# charger_1_2.net
KiCad netlist of a schematic drawn in EAGLE
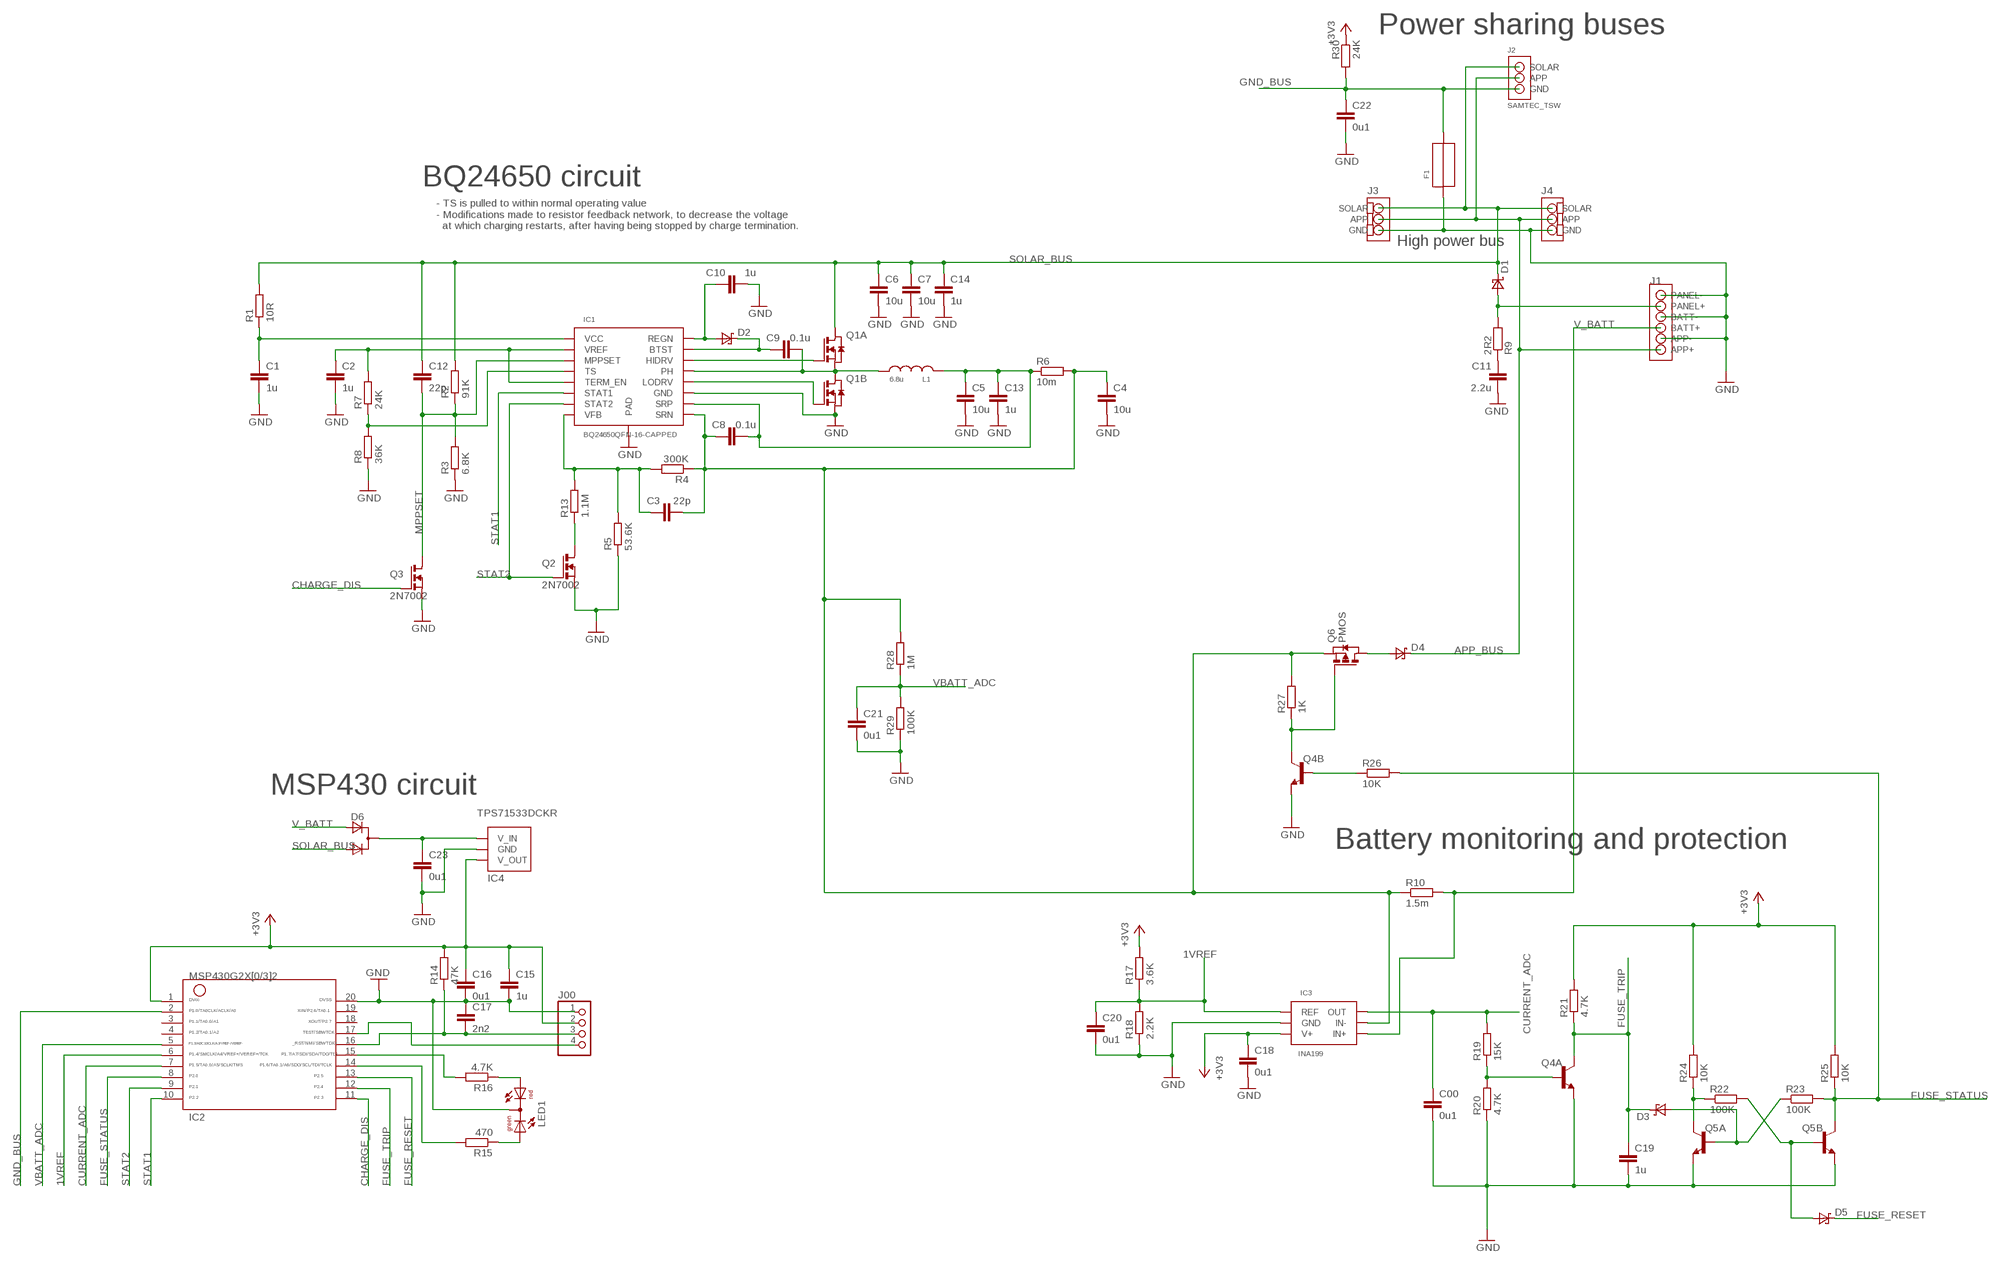
[diagram p0: schematic, sheet 1]

(export (version "E")
  (design (tool "Eeschema 10.0.6"))
  (components
    (comp (ref "C00")
      (value "0u1")
      (footprint "eagle-import:C0603K")
      (libsource (lib "eagle-import") (part "C-EUC0603K"))
    )
    (comp (ref "C1")
      (value "1u")
      (footprint "eagle-import:C0603")
      (libsource (lib "eagle-import") (part "C-EUC0603"))
    )
    (comp (ref "C2")
      (value "1u")
      (footprint "eagle-import:C0603")
      (libsource (lib "eagle-import") (part "C-EUC0603"))
    )
    (comp (ref "C3")
      (value "22p")
      (footprint "eagle-import:C0603")
      (libsource (lib "eagle-import") (part "C-EUC0603"))
    )
    (comp (ref "C4")
      (value "10u")
      (footprint "eagle-import:C1206")
      (libsource (lib "eagle-import") (part "C-EUC1206"))
    )
    (comp (ref "C5")
      (value "10u")
      (footprint "eagle-import:C1206")
      (libsource (lib "eagle-import") (part "C-EUC1206"))
    )
    (comp (ref "C6")
      (value "10u")
      (footprint "eagle-import:C1206")
      (libsource (lib "eagle-import") (part "C-EUC1206"))
    )
    (comp (ref "C7")
      (value "10u")
      (footprint "eagle-import:C1206")
      (libsource (lib "eagle-import") (part "C-EUC1206"))
    )
    (comp (ref "C8")
      (value "0.1u")
      (footprint "eagle-import:C0603")
      (libsource (lib "eagle-import") (part "C-EUC0603"))
    )
    (comp (ref "C9")
      (value "0.1u")
      (footprint "eagle-import:C0603")
      (libsource (lib "eagle-import") (part "C-EUC0603"))
    )
    (comp (ref "C10")
      (value "1u")
      (footprint "eagle-import:C0603")
      (libsource (lib "eagle-import") (part "C-EUC0603"))
    )
    (comp (ref "C11")
      (value "2.2u")
      (footprint "eagle-import:C0603")
      (libsource (lib "eagle-import") (part "C-EUC0603"))
    )
    (comp (ref "C12")
      (value "22p")
      (footprint "eagle-import:C0603")
      (libsource (lib "eagle-import") (part "C-EUC0603"))
    )
    (comp (ref "C13")
      (value "1u")
      (footprint "eagle-import:C0603")
      (libsource (lib "eagle-import") (part "C-EUC0603"))
    )
    (comp (ref "C14")
      (value "1u")
      (footprint "eagle-import:C0603")
      (libsource (lib "eagle-import") (part "C-EUC0603"))
    )
    (comp (ref "C15")
      (value "1u")
      (footprint "eagle-import:C0603K")
      (libsource (lib "eagle-import") (part "C-EUC0603K"))
    )
    (comp (ref "C16")
      (value "0u1")
      (footprint "eagle-import:C0603K")
      (libsource (lib "eagle-import") (part "C-EUC0603K"))
    )
    (comp (ref "C17")
      (value "2n2")
      (footprint "eagle-import:C0603K")
      (libsource (lib "eagle-import") (part "C-EUC0603K"))
    )
    (comp (ref "C18")
      (value "0u1")
      (footprint "eagle-import:C0603K")
      (libsource (lib "eagle-import") (part "C-EUC0603K"))
    )
    (comp (ref "C19")
      (value "1u")
      (footprint "eagle-import:C0603")
      (libsource (lib "eagle-import") (part "C-EUC0603"))
    )
    (comp (ref "C20")
      (value "0u1")
      (footprint "eagle-import:C0603K")
      (libsource (lib "eagle-import") (part "C-EUC0603K"))
    )
    (comp (ref "C21")
      (value "0u1")
      (footprint "eagle-import:C0603K")
      (libsource (lib "eagle-import") (part "C-EUC0603K"))
    )
    (comp (ref "C22")
      (value "0u1")
      (footprint "eagle-import:C0603K")
      (libsource (lib "eagle-import") (part "C-EUC0603K"))
    )
    (comp (ref "C23")
      (value "0u1")
      (footprint "eagle-import:C0603K")
      (libsource (lib "eagle-import") (part "C-EUC0603K"))
    )
    (comp (ref "D1")
      (value "SCHOTTKYDPAK")
      (footprint "eagle-import:DPAK")
      (libsource (lib "eagle-import") (part "SCHOTTKYDPAK"))
    )
    (comp (ref "D2")
      (value "SCHOTTKYSOT23")
      (footprint "eagle-import:SOT23")
      (libsource (lib "eagle-import") (part "SCHOTTKYSOT23"))
    )
    (comp (ref "D3")
      (value "SCHOTTKYSOD-523F")
      (footprint "eagle-import:SOD-523F")
      (libsource (lib "eagle-import") (part "SCHOTTKYSOD-523F"))
    )
    (comp (ref "D4")
      (value "SCHOTTKYSO8-FLAT")
      (footprint "eagle-import:SO8-FLAT")
      (libsource (lib "eagle-import") (part "SCHOTTKYSO8-FLAT"))
    )
    (comp (ref "D5")
      (value "SCHOTTKYSOD-523F")
      (footprint "eagle-import:SOD-523F")
      (libsource (lib "eagle-import") (part "SCHOTTKYSOD-523F"))
    )
    (comp (ref "D6")
      (value "D_2ASOT23")
      (footprint "eagle-import:SOT-23")
      (libsource (lib "eagle-import") (part "D_2ASOT23"))
    )
    (comp (ref "F1")
      (value "FUSE2920")
      (footprint "eagle-import:2920")
      (libsource (lib "eagle-import") (part "FUSE2920"))
    )
    (comp (ref "IC1")
      (value "BQ24650QFN-16-CAPPED")
      (footprint "eagle-import:QFN-16-CAPPED")
      (libsource (lib "eagle-import") (part "BQ24650QFN-16-CAPPED"))
    )
    (comp (ref "IC2")
      (value "G2X[0/3]2---PW20")
      (footprint "eagle-import:PW20")
      (libsource (lib "eagle-import") (part "G2X[0/3]2---PW20"))
    )
    (comp (ref "IC3")
      (value "INA199")
      (footprint "eagle-import:SC70-6")
      (libsource (lib "eagle-import") (part "INA199"))
    )
    (comp (ref "IC4")
      (value "TPS71533DCKR")
      (footprint "eagle-import:SC70-5")
      (libsource (lib "eagle-import") (part "TPS71533DCKR"))
    )
    (comp (ref "J00")
      (value "PINHD-1X4")
      (footprint "eagle-import:1X04")
      (libsource (lib "eagle-import") (part "PINHD-1X4"))
    )
    (comp (ref "J1")
      (value "TERMINALBLOCK")
      (footprint "eagle-import:TERMINALBLOCK")
      (libsource (lib "eagle-import") (part "TERMINALBLOCK"))
    )
    (comp (ref "J2")
      (value "SAMTEC_TSW")
      (footprint "eagle-import:SAMTEC_TSW")
      (libsource (lib "eagle-import") (part "SAMTEC_TSW"))
    )
    (comp (ref "J3")
      (value "TERMINALBLOCK_3_REV")
      (footprint "eagle-import:TERMINALBLOCK_3_REV")
      (libsource (lib "eagle-import") (part "TERMINALBLOCK_3_REV"))
    )
    (comp (ref "J4")
      (value "TERMINALBLOCK_3")
      (footprint "eagle-import:TERMINALBLOCK_3")
      (libsource (lib "eagle-import") (part "TERMINALBLOCK_3"))
    )
    (comp (ref "L1")
      (value "6.8u")
      (footprint "eagle-import:INDUCTOR")
      (libsource (lib "eagle-import") (part "MULTICOMPINDUCTOR"))
    )
    (comp (ref "LED1")
      (value "DUOLED5MM")
      (footprint "eagle-import:DUOLED5MM")
      (libsource (lib "eagle-import") (part "DUOLED5MM"))
    )
    (comp (ref "Q1")
      (value "SI7288DP")
      (footprint "eagle-import:POWERPAK-SO8-DUAL")
      (libsource (lib "eagle-import") (part "SI7288DP"))
    )
    (comp (ref "Q2")
      (value "2N7002")
      (footprint "eagle-import:SOT23")
      (libsource (lib "eagle-import") (part "2N7002"))
    )
    (comp (ref "Q3")
      (value "2N7002")
      (footprint "eagle-import:SOT23")
      (libsource (lib "eagle-import") (part "2N7002"))
    )
    (comp (ref "Q4")
      (value "DUALNPN")
      (footprint "eagle-import:SC70-6")
      (libsource (lib "eagle-import") (part "DUALNPN"))
    )
    (comp (ref "Q5")
      (value "DUALNPN")
      (footprint "eagle-import:SC70-6")
      (libsource (lib "eagle-import") (part "DUALNPN"))
    )
    (comp (ref "Q6")
      (value "PMOS")
      (footprint "eagle-import:POWERPAK-SO8")
      (libsource (lib "eagle-import") (part "PMOS"))
    )
    (comp (ref "R1")
      (value "10R")
      (footprint "eagle-import:R0603")
      (libsource (lib "eagle-import") (part "R-EU_R0603"))
    )
    (comp (ref "R2")
      (value "91K")
      (footprint "eagle-import:R0603")
      (libsource (lib "eagle-import") (part "R-EU_R0603"))
    )
    (comp (ref "R3")
      (value "6.8K")
      (footprint "eagle-import:R0603")
      (libsource (lib "eagle-import") (part "R-EU_R0603"))
    )
    (comp (ref "R4")
      (value "300K")
      (footprint "eagle-import:R0603")
      (libsource (lib "eagle-import") (part "R-EU_R0603"))
    )
    (comp (ref "R5")
      (value "53.6K")
      (footprint "eagle-import:R0805")
      (libsource (lib "eagle-import") (part "R-EU_R0805"))
    )
    (comp (ref "R6")
      (value "10m")
      (footprint "eagle-import:R1206")
      (libsource (lib "eagle-import") (part "R-EU_R1206"))
    )
    (comp (ref "R7")
      (value "24K")
      (footprint "eagle-import:R0603")
      (libsource (lib "eagle-import") (part "R-EU_R0603"))
    )
    (comp (ref "R8")
      (value "36K")
      (footprint "eagle-import:R0603")
      (libsource (lib "eagle-import") (part "R-EU_R0603"))
    )
    (comp (ref "R9")
      (value "2R2")
      (footprint "eagle-import:R0603")
      (libsource (lib "eagle-import") (part "R-EU_R0603"))
    )
    (comp (ref "R10")
      (value "1.5m")
      (footprint "eagle-import:R2010")
      (libsource (lib "eagle-import") (part "R-EU_R2010"))
    )
    (comp (ref "R13")
      (value "1.1M")
      (footprint "eagle-import:R0603")
      (libsource (lib "eagle-import") (part "R-EU_R0603"))
    )
    (comp (ref "R14")
      (value "47K")
      (footprint "eagle-import:R0603")
      (libsource (lib "eagle-import") (part "R-EU_R0603"))
    )
    (comp (ref "R15")
      (value "470")
      (footprint "eagle-import:R0603")
      (libsource (lib "eagle-import") (part "resistor_R-EU_R0603"))
    )
    (comp (ref "R16")
      (value "4.7K")
      (footprint "eagle-import:R0603")
      (libsource (lib "eagle-import") (part "resistor_R-EU_R0603"))
    )
    (comp (ref "R17")
      (value "3.6K")
      (footprint "eagle-import:R0603")
      (libsource (lib "eagle-import") (part "R-EU_R0603"))
    )
    (comp (ref "R18")
      (value "2.2K")
      (footprint "eagle-import:R0603")
      (libsource (lib "eagle-import") (part "R-EU_R0603"))
    )
    (comp (ref "R19")
      (value "15K")
      (footprint "eagle-import:R0603")
      (libsource (lib "eagle-import") (part "R-EU_R0603"))
    )
    (comp (ref "R20")
      (value "4.7K")
      (footprint "eagle-import:R0603")
      (libsource (lib "eagle-import") (part "R-EU_R0603"))
    )
    (comp (ref "R21")
      (value "4.7K")
      (footprint "eagle-import:R0603")
      (libsource (lib "eagle-import") (part "R-EU_R0603"))
    )
    (comp (ref "R22")
      (value "100K")
      (footprint "eagle-import:R0603")
      (libsource (lib "eagle-import") (part "R-EU_R0603"))
    )
    (comp (ref "R23")
      (value "100K")
      (footprint "eagle-import:R0603")
      (libsource (lib "eagle-import") (part "R-EU_R0603"))
    )
    (comp (ref "R24")
      (value "10K")
      (footprint "eagle-import:R0603")
      (libsource (lib "eagle-import") (part "R-EU_R0603"))
    )
    (comp (ref "R25")
      (value "10K")
      (footprint "eagle-import:R0603")
      (libsource (lib "eagle-import") (part "R-EU_R0603"))
    )
    (comp (ref "R26")
      (value "10K")
      (footprint "eagle-import:R0603")
      (libsource (lib "eagle-import") (part "R-EU_R0603"))
    )
    (comp (ref "R27")
      (value "1K")
      (footprint "eagle-import:R0603")
      (libsource (lib "eagle-import") (part "R-EU_R0603"))
    )
    (comp (ref "R28")
      (value "1M")
      (footprint "eagle-import:R0805")
      (libsource (lib "eagle-import") (part "R-EU_R0805"))
    )
    (comp (ref "R29")
      (value "100K")
      (footprint "eagle-import:R0603")
      (libsource (lib "eagle-import") (part "R-EU_R0603"))
    )
    (comp (ref "R30")
      (value "24K")
      (footprint "eagle-import:R0603")
      (libsource (lib "eagle-import") (part "R-EU_R0603"))
    )
  )
  (nets
    (net (code "1") (name "+3V3") (class "Default")
      (node (ref "C15") (pin "1") (pinfunction "1_1") (pintype "passive"))
      (node (ref "C16") (pin "1") (pinfunction "1_1") (pintype "passive"))
      (node (ref "C18") (pin "1") (pinfunction "1_1") (pintype "passive"))
      (node (ref "IC2") (pin "1") (pinfunction "1_1") (pintype "bidirectional"))
      (node (ref "IC3") (pin "COLLECTOR-A-3") (pinfunction "V+_COLLECTOR-A-3") (pintype "bidirectional"))
      (node (ref "IC4") (pin "OUT") (pinfunction "V_OUT_OUT") (pintype "bidirectional"))
      (node (ref "J00") (pin "2") (pinfunction "2_2") (pintype "passive"))
      (node (ref "R14") (pin "2") (pinfunction "2_2") (pintype "passive"))
      (node (ref "R17") (pin "2") (pinfunction "2_2") (pintype "passive"))
      (node (ref "R21") (pin "2") (pinfunction "2_2") (pintype "passive"))
      (node (ref "R24") (pin "2") (pinfunction "2_2") (pintype "passive"))
      (node (ref "R25") (pin "2") (pinfunction "2_2") (pintype "passive"))
      (node (ref "R30") (pin "1") (pinfunction "1_1") (pintype "passive"))
    )
    (net (code "2") (name "/1VREF") (class "Default")
      (node (ref "C20") (pin "1") (pinfunction "1_1") (pintype "passive"))
      (node (ref "IC2") (pin "6") (pinfunction "6_6") (pintype "bidirectional"))
      (node (ref "IC3") (pin "EMITTER-B-1") (pinfunction "REF_EMITTER-B-1") (pintype "bidirectional"))
      (node (ref "R17") (pin "1") (pinfunction "1_1") (pintype "passive"))
      (node (ref "R18") (pin "2") (pinfunction "2_2") (pintype "passive"))
    )
    (net (code "3") (name "/APP_BUS") (class "Default")
      (node (ref "D4") (pin "CATHODE") (pinfunction "CATHODE_CATHODE") (pintype "passive"))
      (node (ref "J1") (pin "APP+") (pinfunction "APP+_APP+") (pintype "bidirectional"))
      (node (ref "J2") (pin "APP") (pinfunction "APP_APP") (pintype "bidirectional"))
      (node (ref "J3") (pin "APP") (pinfunction "APP_APP") (pintype "bidirectional"))
      (node (ref "J4") (pin "APP") (pinfunction "APP_APP") (pintype "bidirectional"))
    )
    (net (code "4") (name "/CHARGE_DIS") (class "Default")
      (node (ref "IC2") (pin "11") (pinfunction "11_11") (pintype "bidirectional"))
      (node (ref "Q3") (pin "ANODE") (pinfunction "G_ANODE") (pintype "passive"))
    )
    (net (code "5") (name "/CURRENT_ADC") (class "Default")
      (node (ref "C00") (pin "1") (pinfunction "1_1") (pintype "passive"))
      (node (ref "IC2") (pin "7") (pinfunction "7_7") (pintype "bidirectional"))
      (node (ref "IC3") (pin "COLLECTOR-B-6") (pinfunction "OUT_COLLECTOR-B-6") (pintype "bidirectional"))
      (node (ref "R19") (pin "2") (pinfunction "2_2") (pintype "passive"))
    )
    (net (code "6") (name "/FUSE_RESET") (class "Default")
      (node (ref "D5") (pin "CATHODE") (pinfunction "CATHODE_CATHODE") (pintype "passive"))
      (node (ref "IC2") (pin "13") (pinfunction "13_13") (pintype "bidirectional"))
    )
    (net (code "7") (name "/FUSE_STATUS") (class "Default")
      (node (ref "IC2") (pin "8") (pinfunction "8_8") (pintype "bidirectional"))
      (node (ref "Q5") (pin "COLLECTOR-B-6") (pinfunction "COLLECTOR_COLLECTOR-B-6") (pintype "passive"))
      (node (ref "R23") (pin "2") (pinfunction "2_2") (pintype "passive"))
      (node (ref "R25") (pin "1") (pinfunction "1_1") (pintype "passive"))
      (node (ref "R26") (pin "2") (pinfunction "2_2") (pintype "passive"))
    )
    (net (code "8") (name "/FUSE_TRIP") (class "Default")
      (node (ref "C19") (pin "1") (pinfunction "1_1") (pintype "passive"))
      (node (ref "D3") (pin "CATHODE") (pinfunction "CATHODE_CATHODE") (pintype "passive"))
      (node (ref "IC2") (pin "12") (pinfunction "12_12") (pintype "bidirectional"))
      (node (ref "Q4") (pin "COLLECTOR-A-3") (pinfunction "COLLECTOR_COLLECTOR-A-3") (pintype "passive"))
      (node (ref "R21") (pin "1") (pinfunction "1_1") (pintype "passive"))
    )
    (net (code "9") (name "/GND_BUS") (class "Default")
      (node (ref "C22") (pin "1") (pinfunction "1_1") (pintype "passive"))
      (node (ref "F1") (pin "P$2") (pinfunction "P$2_P$2") (pintype "bidirectional"))
      (node (ref "IC2") (pin "2") (pinfunction "2_2") (pintype "bidirectional"))
      (node (ref "J2") (pin "GND") (pinfunction "GND_GND") (pintype "bidirectional"))
      (node (ref "R30") (pin "2") (pinfunction "2_2") (pintype "passive"))
    )
    (net (code "10") (name "/MPPSET") (class "Default")
      (node (ref "C12") (pin "2") (pinfunction "2_2") (pintype "passive"))
      (node (ref "IC1") (pin "MPPSET-P2") (pinfunction "MPPSET_MPPSET-P2") (pintype "bidirectional"))
      (node (ref "Q3") (pin "CATHODE") (pinfunction "D_CATHODE") (pintype "passive"))
      (node (ref "R2") (pin "1") (pinfunction "1_1") (pintype "passive"))
      (node (ref "R3") (pin "2") (pinfunction "2_2") (pintype "passive"))
    )
    (net (code "11") (name "/SOLAR_BUS") (class "Default")
      (node (ref "C12") (pin "1") (pinfunction "1_1") (pintype "passive"))
      (node (ref "C14") (pin "1") (pinfunction "1_1") (pintype "passive"))
      (node (ref "C6") (pin "1") (pinfunction "1_1") (pintype "passive"))
      (node (ref "C7") (pin "1") (pinfunction "1_1") (pintype "passive"))
      (node (ref "D1") (pin "CATHODE") (pinfunction "CATHODE_CATHODE") (pintype "passive"))
      (node (ref "D6") (pin "3") (pinfunction "A2_3") (pintype "passive"))
      (node (ref "J2") (pin "SOLAR") (pinfunction "SOLAR_SOLAR") (pintype "bidirectional"))
      (node (ref "J3") (pin "SOLAR") (pinfunction "SOLAR_SOLAR") (pintype "bidirectional"))
      (node (ref "J4") (pin "SOLAR") (pinfunction "SOLAR_SOLAR") (pintype "bidirectional"))
      (node (ref "Q1") (pin "D1A") (pinfunction "D_D1A") (pintype "passive"))
      (node (ref "Q1") (pin "D1B") (pinfunction "D_D1B") (pintype "passive"))
      (node (ref "Q1") (pin "D1C") (pinfunction "D_D1C") (pintype "passive"))
      (node (ref "R1") (pin "2") (pinfunction "2_2") (pintype "passive"))
      (node (ref "R2") (pin "2") (pinfunction "2_2") (pintype "passive"))
    )
    (net (code "12") (name "/STAT1") (class "Default")
      (node (ref "IC1") (pin "STAT1-P3") (pinfunction "STAT1_STAT1-P3") (pintype "bidirectional"))
      (node (ref "IC2") (pin "10") (pinfunction "10_10") (pintype "bidirectional"))
    )
    (net (code "13") (name "/STAT2") (class "Default")
      (node (ref "IC1") (pin "STAT2-P5") (pinfunction "STAT2_STAT2-P5") (pintype "bidirectional"))
      (node (ref "IC2") (pin "9") (pinfunction "9_9") (pintype "bidirectional"))
      (node (ref "Q2") (pin "ANODE") (pinfunction "G_ANODE") (pintype "passive"))
    )
    (net (code "14") (name "/VBATT_ADC") (class "Default")
      (node (ref "C21") (pin "1") (pinfunction "1_1") (pintype "passive"))
      (node (ref "IC2") (pin "5") (pinfunction "5_5") (pintype "bidirectional"))
      (node (ref "R28") (pin "1") (pinfunction "1_1") (pintype "passive"))
      (node (ref "R29") (pin "2") (pinfunction "2_2") (pintype "passive"))
    )
    (net (code "15") (name "/V_BATT") (class "Default")
      (node (ref "D6") (pin "2") (pinfunction "A1_2") (pintype "passive"))
      (node (ref "IC3") (pin "EMMITER-A-4") (pinfunction "IN+_EMMITER-A-4") (pintype "bidirectional"))
      (node (ref "J1") (pin "BATT+") (pinfunction "BATT+_BATT+") (pintype "bidirectional"))
      (node (ref "R10") (pin "2") (pinfunction "2_2") (pintype "passive"))
    )
    (net (code "16") (name "GND") (class "Default")
      (node (ref "C00") (pin "2") (pinfunction "2_2") (pintype "passive"))
      (node (ref "C1") (pin "2") (pinfunction "2_2") (pintype "passive"))
      (node (ref "C10") (pin "2") (pinfunction "2_2") (pintype "passive"))
      (node (ref "C11") (pin "2") (pinfunction "2_2") (pintype "passive"))
      (node (ref "C13") (pin "2") (pinfunction "2_2") (pintype "passive"))
      (node (ref "C14") (pin "2") (pinfunction "2_2") (pintype "passive"))
      (node (ref "C15") (pin "2") (pinfunction "2_2") (pintype "passive"))
      (node (ref "C16") (pin "2") (pinfunction "2_2") (pintype "passive"))
      (node (ref "C17") (pin "1") (pinfunction "1_1") (pintype "passive"))
      (node (ref "C18") (pin "2") (pinfunction "2_2") (pintype "passive"))
      (node (ref "C19") (pin "2") (pinfunction "2_2") (pintype "passive"))
      (node (ref "C2") (pin "2") (pinfunction "2_2") (pintype "passive"))
      (node (ref "C20") (pin "2") (pinfunction "2_2") (pintype "passive"))
      (node (ref "C21") (pin "2") (pinfunction "2_2") (pintype "passive"))
      (node (ref "C22") (pin "2") (pinfunction "2_2") (pintype "passive"))
      (node (ref "C23") (pin "2") (pinfunction "2_2") (pintype "passive"))
      (node (ref "C4") (pin "2") (pinfunction "2_2") (pintype "passive"))
      (node (ref "C5") (pin "2") (pinfunction "2_2") (pintype "passive"))
      (node (ref "C6") (pin "2") (pinfunction "2_2") (pintype "passive"))
      (node (ref "C7") (pin "2") (pinfunction "2_2") (pintype "passive"))
      (node (ref "F1") (pin "P$1") (pinfunction "P$1_P$1") (pintype "bidirectional"))
      (node (ref "IC1") (pin "GND-P11") (pinfunction "GND_GND-P11") (pintype "bidirectional"))
      (node (ref "IC1") (pin "P$17") (pinfunction "PAD_P$17") (pintype "bidirectional"))
      (node (ref "IC1") (pin "P$18") (pinfunction "PAD_P$18") (pintype "bidirectional"))
      (node (ref "IC1") (pin "P$19") (pinfunction "PAD_P$19") (pintype "bidirectional"))
      (node (ref "IC1") (pin "P$20") (pinfunction "PAD_P$20") (pintype "bidirectional"))
      (node (ref "IC2") (pin "20") (pinfunction "20_20") (pintype "bidirectional"))
      (node (ref "IC3") (pin "BASE-B-2") (pinfunction "GND_BASE-B-2") (pintype "bidirectional"))
      (node (ref "IC4") (pin "GND") (pinfunction "GND_GND") (pintype "bidirectional"))
      (node (ref "J00") (pin "1") (pinfunction "1_1") (pintype "passive"))
      (node (ref "J1") (pin "APP-") (pinfunction "APP-_APP-") (pintype "bidirectional"))
      (node (ref "J1") (pin "BATT-") (pinfunction "BATT-_BATT-") (pintype "bidirectional"))
      (node (ref "J1") (pin "PANEL-") (pinfunction "PANEL-_PANEL-") (pintype "bidirectional"))
      (node (ref "J3") (pin "GND") (pinfunction "GND_GND") (pintype "bidirectional"))
      (node (ref "J4") (pin "GND") (pinfunction "GND_GND") (pintype "bidirectional"))
      (node (ref "LED1") (pin "K") (pinfunction "C_K") (pintype "passive"))
      (node (ref "Q1") (pin "S2") (pinfunction "S_S2") (pintype "passive"))
      (node (ref "Q2") (pin "NC") (pinfunction "S_NC") (pintype "passive"))
      (node (ref "Q3") (pin "NC") (pinfunction "S_NC") (pintype "passive"))
      (node (ref "Q4") (pin "EMITTER-B-1") (pinfunction "EMMITER_EMITTER-B-1") (pintype "passive"))
      (node (ref "Q4") (pin "EMMITER-A-4") (pinfunction "EMMITER_EMMITER-A-4") (pintype "passive"))
      (node (ref "Q5") (pin "EMITTER-B-1") (pinfunction "EMMITER_EMITTER-B-1") (pintype "passive"))
      (node (ref "Q5") (pin "EMMITER-A-4") (pinfunction "EMMITER_EMMITER-A-4") (pintype "passive"))
      (node (ref "R18") (pin "1") (pinfunction "1_1") (pintype "passive"))
      (node (ref "R20") (pin "1") (pinfunction "1_1") (pintype "passive"))
      (node (ref "R29") (pin "1") (pinfunction "1_1") (pintype "passive"))
      (node (ref "R3") (pin "1") (pinfunction "1_1") (pintype "passive"))
      (node (ref "R5") (pin "1") (pinfunction "1_1") (pintype "passive"))
      (node (ref "R8") (pin "1") (pinfunction "1_1") (pintype "passive"))
    )
    (net (code "17") (name "Net-(C11-Pad1)") (class "Default")
      (node (ref "C11") (pin "1") (pinfunction "1_1") (pintype "passive"))
      (node (ref "R9") (pin "1") (pinfunction "1_1") (pintype "passive"))
    )
    (net (code "18") (name "Net-(C17-Pad2)") (class "Default")
      (node (ref "C17") (pin "2") (pinfunction "2_2") (pintype "passive"))
      (node (ref "IC2") (pin "16") (pinfunction "16_16") (pintype "bidirectional"))
      (node (ref "J00") (pin "3") (pinfunction "3_3") (pintype "passive"))
      (node (ref "R14") (pin "1") (pinfunction "1_1") (pintype "passive"))
    )
    (net (code "19") (name "Net-(D1-ANODE-PadANODE1)") (class "Default")
      (node (ref "D1") (pin "ANODE1") (pinfunction "ANODE_ANODE1") (pintype "passive"))
      (node (ref "D1") (pin "ANODE2") (pinfunction "ANODE_ANODE2") (pintype "passive"))
      (node (ref "J1") (pin "PANEL+") (pinfunction "PANEL+_PANEL+") (pintype "bidirectional"))
      (node (ref "R9") (pin "2") (pinfunction "2_2") (pintype "passive"))
    )
    (net (code "20") (name "Net-(D4-ANODE-PadANODE1)") (class "Default")
      (node (ref "D4") (pin "ANODE1") (pinfunction "ANODE_ANODE1") (pintype "passive"))
      (node (ref "D4") (pin "ANODE2") (pinfunction "ANODE_ANODE2") (pintype "passive"))
      (node (ref "D4") (pin "ANODE3") (pinfunction "ANODE_ANODE3") (pintype "passive"))
      (node (ref "Q6") (pin "D1") (pinfunction "D_D1") (pintype "passive"))
      (node (ref "Q6") (pin "D2") (pinfunction "D_D2") (pintype "passive"))
      (node (ref "Q6") (pin "D3") (pinfunction "D_D3") (pintype "passive"))
      (node (ref "Q6") (pin "D4") (pinfunction "D_D4") (pintype "passive"))
    )
    (net (code "21") (name "Net-(D6-C)") (class "Default")
      (node (ref "C23") (pin "1") (pinfunction "1_1") (pintype "passive"))
      (node (ref "D6") (pin "1") (pinfunction "C_1") (pintype "passive"))
      (node (ref "IC4") (pin "IN") (pinfunction "V_IN_IN") (pintype "bidirectional"))
    )
    (net (code "22") (name "Net-(IC1-BTST)") (class "Default")
      (node (ref "C9") (pin "1") (pinfunction "1_1") (pintype "passive"))
      (node (ref "D2") (pin "CATHODE") (pinfunction "CATHODE_CATHODE") (pintype "passive"))
      (node (ref "IC1") (pin "BTST-P16") (pinfunction "BTST_BTST-P16") (pintype "bidirectional"))
    )
    (net (code "23") (name "Net-(IC1-HIDRV)") (class "Default")
      (node (ref "IC1") (pin "HIDRV-P15") (pinfunction "HIDRV_HIDRV-P15") (pintype "bidirectional"))
      (node (ref "Q1") (pin "G1") (pinfunction "G_G1") (pintype "passive"))
    )
    (net (code "24") (name "Net-(IC1-LODRV)") (class "Default")
      (node (ref "IC1") (pin "LODRV-P13") (pinfunction "LODRV_LODRV-P13") (pintype "bidirectional"))
      (node (ref "Q1") (pin "G2") (pinfunction "G_G2") (pintype "passive"))
    )
    (net (code "25") (name "Net-(IC1-PH)") (class "Default")
      (node (ref "C9") (pin "2") (pinfunction "2_2") (pintype "passive"))
      (node (ref "IC1") (pin "PH-P14") (pinfunction "PH_PH-P14") (pintype "bidirectional"))
      (node (ref "L1") (pin "P$2") (pinfunction "P$2_P$2") (pintype "bidirectional"))
      (node (ref "Q1") (pin "D2A") (pinfunction "D_D2A") (pintype "passive"))
      (node (ref "Q1") (pin "D2B") (pinfunction "D_D2B") (pintype "passive"))
      (node (ref "Q1") (pin "D2C") (pinfunction "D_D2C") (pintype "passive"))
      (node (ref "Q1") (pin "S1") (pinfunction "S_S1") (pintype "passive"))
    )
    (net (code "26") (name "Net-(IC1-REGN)") (class "Default")
      (node (ref "C10") (pin "1") (pinfunction "1_1") (pintype "passive"))
      (node (ref "D2") (pin "ANODE") (pinfunction "ANODE_ANODE") (pintype "passive"))
      (node (ref "IC1") (pin "REGN-P12") (pinfunction "REGN_REGN-P12") (pintype "bidirectional"))
    )
    (net (code "27") (name "Net-(IC1-SRN)") (class "Default")
      (node (ref "C3") (pin "2") (pinfunction "2_2") (pintype "passive"))
      (node (ref "C4") (pin "1") (pinfunction "1_1") (pintype "passive"))
      (node (ref "C8") (pin "1") (pinfunction "1_1") (pintype "passive"))
      (node (ref "IC1") (pin "SRN-P9") (pinfunction "SRN_SRN-P9") (pintype "bidirectional"))
      (node (ref "IC3") (pin "BASE-A-5") (pinfunction "IN-_BASE-A-5") (pintype "bidirectional"))
      (node (ref "Q6") (pin "S1") (pinfunction "S_S1") (pintype "passive"))
      (node (ref "Q6") (pin "S2") (pinfunction "S_S2") (pintype "passive"))
      (node (ref "Q6") (pin "S3") (pinfunction "S_S3") (pintype "passive"))
      (node (ref "R10") (pin "1") (pinfunction "1_1") (pintype "passive"))
      (node (ref "R27") (pin "2") (pinfunction "2_2") (pintype "passive"))
      (node (ref "R28") (pin "2") (pinfunction "2_2") (pintype "passive"))
      (node (ref "R4") (pin "1") (pinfunction "1_1") (pintype "passive"))
      (node (ref "R6") (pin "2") (pinfunction "2_2") (pintype "passive"))
    )
    (net (code "28") (name "Net-(IC1-SRP)") (class "Default")
      (node (ref "C13") (pin "1") (pinfunction "1_1") (pintype "passive"))
      (node (ref "C5") (pin "1") (pinfunction "1_1") (pintype "passive"))
      (node (ref "C8") (pin "2") (pinfunction "2_2") (pintype "passive"))
      (node (ref "IC1") (pin "SRP-P10") (pinfunction "SRP_SRP-P10") (pintype "bidirectional"))
      (node (ref "L1") (pin "P$1") (pinfunction "P$1_P$1") (pintype "bidirectional"))
      (node (ref "R6") (pin "1") (pinfunction "1_1") (pintype "passive"))
    )
    (net (code "29") (name "Net-(IC1-TERM_EN)") (class "Default")
      (node (ref "C2") (pin "1") (pinfunction "1_1") (pintype "passive"))
      (node (ref "IC1") (pin "TERM_EN-P7") (pinfunction "TERM_EN_TERM_EN-P7") (pintype "bidirectional"))
      (node (ref "IC1") (pin "VREF-P6") (pinfunction "VREF_VREF-P6") (pintype "bidirectional"))
      (node (ref "R7") (pin "2") (pinfunction "2_2") (pintype "passive"))
    )
    (net (code "30") (name "Net-(IC1-TS)") (class "Default")
      (node (ref "IC1") (pin "TS-P4") (pinfunction "TS_TS-P4") (pintype "bidirectional"))
      (node (ref "R7") (pin "1") (pinfunction "1_1") (pintype "passive"))
      (node (ref "R8") (pin "2") (pinfunction "2_2") (pintype "passive"))
    )
    (net (code "31") (name "Net-(IC1-VCC)") (class "Default")
      (node (ref "C1") (pin "1") (pinfunction "1_1") (pintype "passive"))
      (node (ref "IC1") (pin "VCC-P1") (pinfunction "VCC_VCC-P1") (pintype "bidirectional"))
      (node (ref "R1") (pin "1") (pinfunction "1_1") (pintype "passive"))
    )
    (net (code "32") (name "Net-(IC1-VFB)") (class "Default")
      (node (ref "C3") (pin "1") (pinfunction "1_1") (pintype "passive"))
      (node (ref "IC1") (pin "VFB-P8") (pinfunction "VFB_VFB-P8") (pintype "bidirectional"))
      (node (ref "R13") (pin "2") (pinfunction "2_2") (pintype "passive"))
      (node (ref "R4") (pin "2") (pinfunction "2_2") (pintype "passive"))
      (node (ref "R5") (pin "2") (pinfunction "2_2") (pintype "passive"))
    )
    (net (code "33") (name "Net-(IC2-Pad14)") (class "Default")
      (node (ref "IC2") (pin "14") (pinfunction "14_14") (pintype "bidirectional"))
      (node (ref "R15") (pin "2") (pinfunction "2_2") (pintype "passive"))
    )
    (net (code "34") (name "Net-(IC2-Pad15)") (class "Default")
      (node (ref "IC2") (pin "15") (pinfunction "15_15") (pintype "bidirectional"))
      (node (ref "R16") (pin "2") (pinfunction "2_2") (pintype "passive"))
    )
    (net (code "35") (name "Net-(IC2-Pad17)") (class "Default")
      (node (ref "IC2") (pin "17") (pinfunction "17_17") (pintype "bidirectional"))
      (node (ref "J00") (pin "4") (pinfunction "4_4") (pintype "passive"))
    )
    (net (code "36") (name "Net-(LED1-PadAG)") (class "Default")
      (node (ref "LED1") (pin "AG") (pinfunction "AG_AG") (pintype "passive"))
      (node (ref "R15") (pin "1") (pinfunction "1_1") (pintype "passive"))
    )
    (net (code "37") (name "Net-(LED1-PadAR)") (class "Default")
      (node (ref "LED1") (pin "AR") (pinfunction "AR_AR") (pintype "passive"))
      (node (ref "R16") (pin "1") (pinfunction "1_1") (pintype "passive"))
    )
    (net (code "38") (name "Net-(Q2-D)") (class "Default")
      (node (ref "Q2") (pin "CATHODE") (pinfunction "D_CATHODE") (pintype "passive"))
      (node (ref "R13") (pin "1") (pinfunction "1_1") (pintype "passive"))
    )
    (net (code "39") (name "Net-(Q4A-BASE)") (class "Default")
      (node (ref "Q4") (pin "BASE-A-5") (pinfunction "BASE_BASE-A-5") (pintype "passive"))
      (node (ref "R19") (pin "1") (pinfunction "1_1") (pintype "passive"))
      (node (ref "R20") (pin "2") (pinfunction "2_2") (pintype "passive"))
    )
    (net (code "40") (name "Net-(Q4B-BASE)") (class "Default")
      (node (ref "Q4") (pin "BASE-B-2") (pinfunction "BASE_BASE-B-2") (pintype "passive"))
      (node (ref "R26") (pin "1") (pinfunction "1_1") (pintype "passive"))
    )
    (net (code "41") (name "Net-(Q4B-COLLECTOR)") (class "Default")
      (node (ref "Q4") (pin "COLLECTOR-B-6") (pinfunction "COLLECTOR_COLLECTOR-B-6") (pintype "passive"))
      (node (ref "Q6") (pin "G") (pinfunction "G_G") (pintype "passive"))
      (node (ref "R27") (pin "1") (pinfunction "1_1") (pintype "passive"))
    )
    (net (code "42") (name "Net-(Q5A-BASE)") (class "Default")
      (node (ref "D3") (pin "ANODE") (pinfunction "ANODE_ANODE") (pintype "passive"))
      (node (ref "Q5") (pin "BASE-A-5") (pinfunction "BASE_BASE-A-5") (pintype "passive"))
      (node (ref "R23") (pin "1") (pinfunction "1_1") (pintype "passive"))
    )
    (net (code "43") (name "Net-(Q5A-COLLECTOR)") (class "Default")
      (node (ref "Q5") (pin "COLLECTOR-A-3") (pinfunction "COLLECTOR_COLLECTOR-A-3") (pintype "passive"))
      (node (ref "R22") (pin "1") (pinfunction "1_1") (pintype "passive"))
      (node (ref "R24") (pin "1") (pinfunction "1_1") (pintype "passive"))
    )
    (net (code "44") (name "Net-(Q5B-BASE)") (class "Default")
      (node (ref "D5") (pin "ANODE") (pinfunction "ANODE_ANODE") (pintype "passive"))
      (node (ref "Q5") (pin "BASE-B-2") (pinfunction "BASE_BASE-B-2") (pintype "passive"))
      (node (ref "R22") (pin "2") (pinfunction "2_2") (pintype "passive"))
    )
    (net (code "45") (name "unconnected-(IC2-Pad3)") (class "Default")
      (node (ref "IC2") (pin "3") (pinfunction "3_3") (pintype "bidirectional"))
    )
    (net (code "46") (name "unconnected-(IC2-Pad4)") (class "Default")
      (node (ref "IC2") (pin "4") (pinfunction "4_4") (pintype "bidirectional"))
    )
    (net (code "47") (name "unconnected-(IC2-Pad18)") (class "Default")
      (node (ref "IC2") (pin "18") (pinfunction "18_18") (pintype "bidirectional"))
    )
    (net (code "48") (name "unconnected-(IC2-Pad19)") (class "Default")
      (node (ref "IC2") (pin "19") (pinfunction "19_19") (pintype "bidirectional"))
    )
  )
)
